# RaspiLink.net
KiCad netlist of a schematic drawn in EAGLE
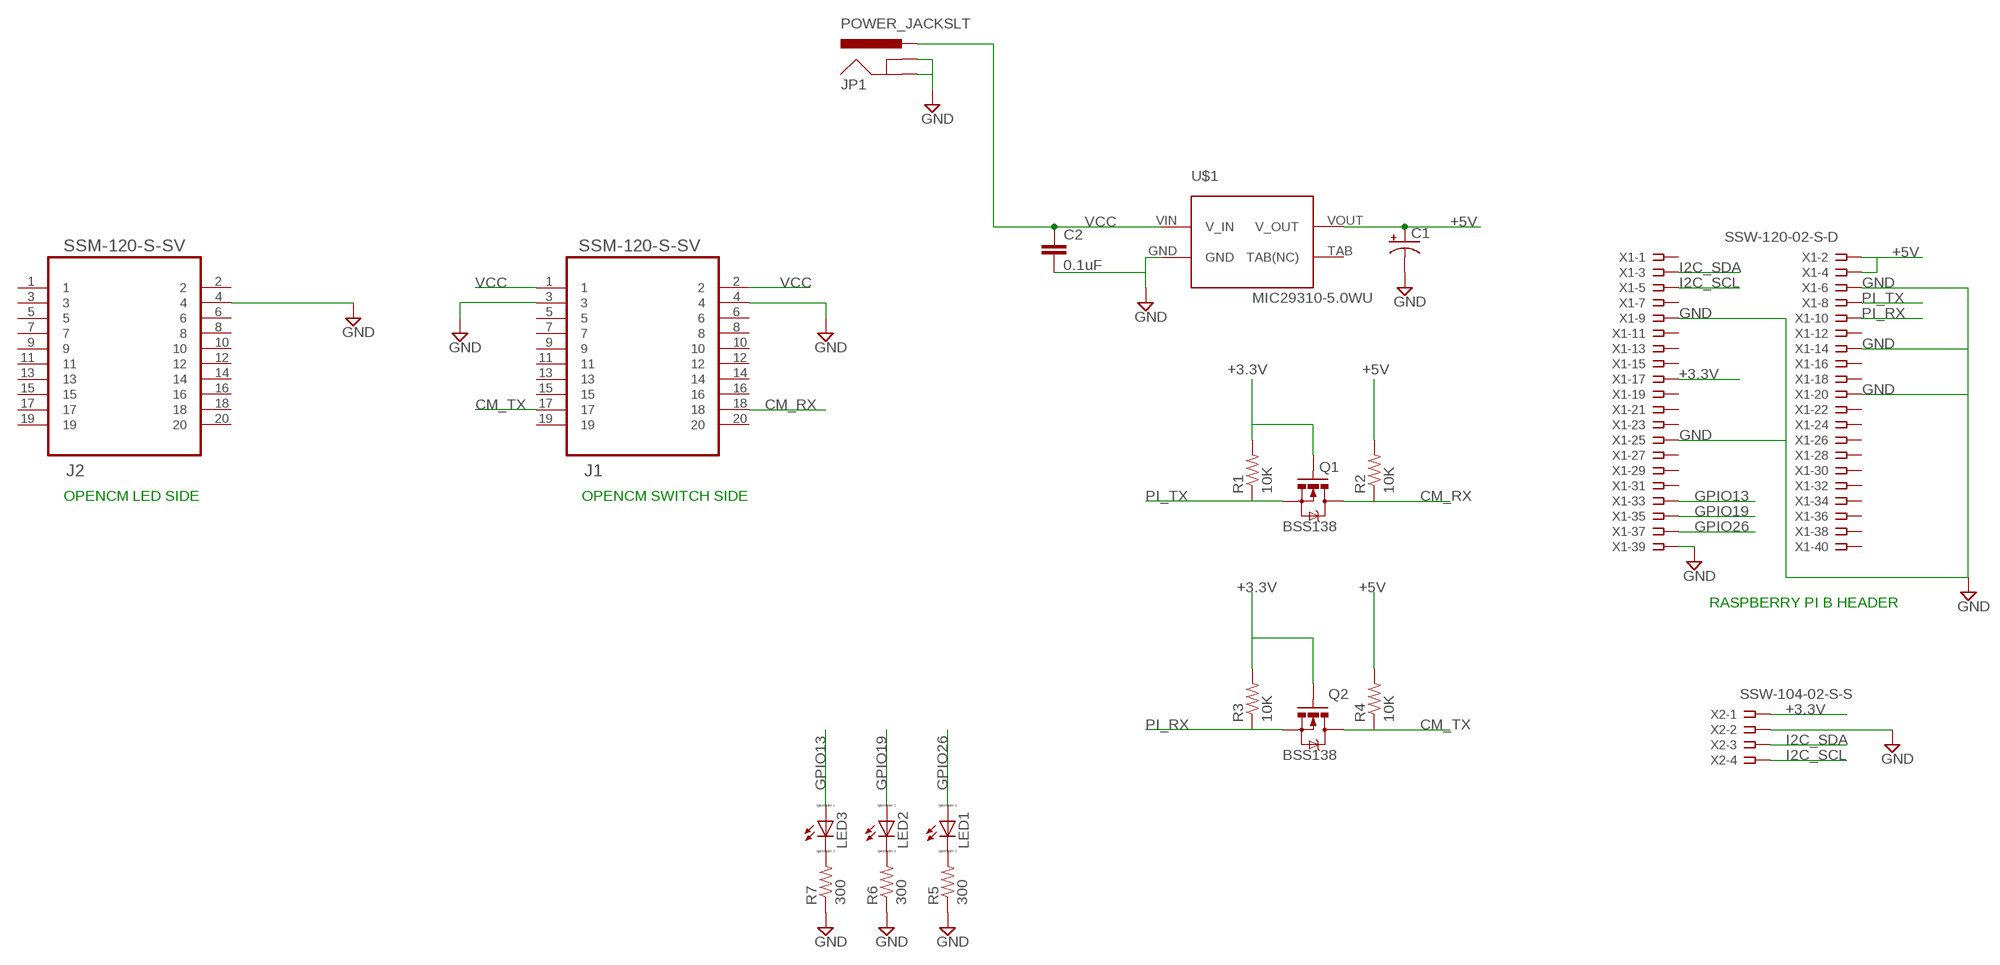
[diagram p0: schematic, sheet 1]

(export (version "E")
  (design (tool "Eeschema 10.0.6"))
  (components
    (comp (ref "C1")
      (value "100UF-25V-20%(PTH)")
      (footprint "eagle-import:CPOL-RADIAL-100UF-25V")
      (libsource (lib "eagle-import") (part "100UF-25V-20%(PTH)"))
    )
    (comp (ref "C2")
      (value "0.1uF")
      (footprint "eagle-import:0603-CAP")
      (libsource (lib "eagle-import") (part "0.1UF-25V-5%(0603)"))
    )
    (comp (ref "J1")
      (value "SSM-120-S-SV")
      (footprint "eagle-import:SAMTEC_SSM-120-S-SV")
      (libsource (lib "eagle-import") (part "SSM-120-S-SV"))
    )
    (comp (ref "J2")
      (value "SSM-120-S-SV")
      (footprint "eagle-import:SAMTEC_SSM-120-S-SV")
      (libsource (lib "eagle-import") (part "SSM-120-S-SV"))
    )
    (comp (ref "JP1")
      (value "POWER_JACKSLT")
      (footprint "eagle-import:POWER_JACK_SLOT")
      (libsource (lib "eagle-import") (part "POWER_JACKSLT"))
    )
    (comp (ref "LED1")
      (value "LED_ELD260")
      (footprint "eagle-import:LED_LD260")
      (libsource (lib "eagle-import") (part "LED_ELD260"))
    )
    (comp (ref "LED2")
      (value "LED_ELD260")
      (footprint "eagle-import:LED_LD260")
      (libsource (lib "eagle-import") (part "LED_ELD260"))
    )
    (comp (ref "LED3")
      (value "LED_ELD260")
      (footprint "eagle-import:LED_LD260")
      (libsource (lib "eagle-import") (part "LED_ELD260"))
    )
    (comp (ref "Q1")
      (value "MOSFET-NCHANNELBSS123LT1G")
      (footprint "eagle-import:SOT23-3")
      (fields (field (name "PROD_ID") "TRANS-08345") (field (name "PROD_ID_1") "BSS138"))
      (libsource (lib "eagle-import") (part "MOSFET-NCHANNELBSS123LT1G"))
    )
    (comp (ref "Q2")
      (value "MOSFET-NCHANNELBSS123LT1G")
      (footprint "eagle-import:SOT23-3")
      (fields (field (name "PROD_ID") "TRANS-08345") (field (name "PROD_ID_1") "BSS138"))
      (libsource (lib "eagle-import") (part "MOSFET-NCHANNELBSS123LT1G"))
    )
    (comp (ref "R1")
      (value "10K")
      (footprint "eagle-import:0603-RES")
      (libsource (lib "eagle-import") (part "RESISTOR0603-RES"))
    )
    (comp (ref "R2")
      (value "10K")
      (footprint "eagle-import:0603-RES")
      (libsource (lib "eagle-import") (part "RESISTOR0603-RES"))
    )
    (comp (ref "R3")
      (value "10K")
      (footprint "eagle-import:0603-RES")
      (libsource (lib "eagle-import") (part "RESISTOR0603-RES"))
    )
    (comp (ref "R4")
      (value "10K")
      (footprint "eagle-import:0603-RES")
      (libsource (lib "eagle-import") (part "RESISTOR0603-RES"))
    )
    (comp (ref "R5")
      (value "300")
      (footprint "eagle-import:0603-RES")
      (libsource (lib "eagle-import") (part "RESISTOR0603-RES"))
    )
    (comp (ref "R6")
      (value "300")
      (footprint "eagle-import:0603-RES")
      (libsource (lib "eagle-import") (part "RESISTOR0603-RES"))
    )
    (comp (ref "R7")
      (value "300")
      (footprint "eagle-import:0603-RES")
      (libsource (lib "eagle-import") (part "RESISTOR0603-RES"))
    )
    (comp (ref "U$1")
      (value "MIC29310-5.0WU")
      (footprint "eagle-import:TO-263-3")
      (libsource (lib "eagle-import") (part "MIC29310-5.0WU"))
    )
    (comp (ref "X1")
      (value "SSW-120-02-S-D")
      (footprint "eagle-import:SSW-120-02-S-D")
      (libsource (lib "eagle-import") (part "SSW-120-02-S-D"))
    )
    (comp (ref "X2")
      (value "SSW-104-02-S-S")
      (footprint "eagle-import:SSW-104-02-S-S")
      (libsource (lib "eagle-import") (part "SSW-104-02-S-S"))
    )
  )
  (nets
    (net (code "1") (name "/+3.3V") (class "Default")
      (node (ref "Q1") (pin "1") (pinfunction "G_1") (pintype "passive"))
      (node (ref "Q2") (pin "1") (pinfunction "G_1") (pintype "passive"))
      (node (ref "R1") (pin "2") (pinfunction "2_2") (pintype "passive"))
      (node (ref "R3") (pin "2") (pinfunction "2_2") (pintype "passive"))
      (node (ref "X1") (pin "17") (pinfunction "1_17") (pintype "passive"))
      (node (ref "X2") (pin "1") (pinfunction "1_1") (pintype "passive"))
    )
    (net (code "2") (name "/+5V") (class "Default")
      (node (ref "C1") (pin "1") (pinfunction "+_1") (pintype "passive"))
      (node (ref "R2") (pin "2") (pinfunction "2_2") (pintype "passive"))
      (node (ref "R4") (pin "2") (pinfunction "2_2") (pintype "passive"))
      (node (ref "U$1") (pin "VOUT") (pinfunction "V_OUT_VOUT") (pintype "bidirectional"))
      (node (ref "X1") (pin "2") (pinfunction "1_2") (pintype "passive"))
      (node (ref "X1") (pin "4") (pinfunction "1_4") (pintype "passive"))
    )
    (net (code "3") (name "/CM_RX") (class "Default")
      (node (ref "J1") (pin "18") (pinfunction "18_18") (pintype "passive"))
      (node (ref "Q1") (pin "3") (pinfunction "D_3") (pintype "passive"))
      (node (ref "R2") (pin "1") (pinfunction "1_1") (pintype "passive"))
    )
    (net (code "4") (name "/CM_TX") (class "Default")
      (node (ref "J1") (pin "17") (pinfunction "17_17") (pintype "passive"))
      (node (ref "Q2") (pin "3") (pinfunction "D_3") (pintype "passive"))
      (node (ref "R4") (pin "1") (pinfunction "1_1") (pintype "passive"))
    )
    (net (code "5") (name "/GPIO13") (class "Default")
      (node (ref "LED3") (pin "A") (pinfunction "A_A") (pintype "passive"))
      (node (ref "X1") (pin "33") (pinfunction "1_33") (pintype "passive"))
    )
    (net (code "6") (name "/GPIO19") (class "Default")
      (node (ref "LED2") (pin "A") (pinfunction "A_A") (pintype "passive"))
      (node (ref "X1") (pin "35") (pinfunction "1_35") (pintype "passive"))
    )
    (net (code "7") (name "/GPIO26") (class "Default")
      (node (ref "LED1") (pin "A") (pinfunction "A_A") (pintype "passive"))
      (node (ref "X1") (pin "37") (pinfunction "1_37") (pintype "passive"))
    )
    (net (code "8") (name "/I2C_SCL") (class "Default")
      (node (ref "X1") (pin "5") (pinfunction "1_5") (pintype "passive"))
      (node (ref "X2") (pin "4") (pinfunction "1_4") (pintype "passive"))
    )
    (net (code "9") (name "/I2C_SDA") (class "Default")
      (node (ref "X1") (pin "3") (pinfunction "1_3") (pintype "passive"))
      (node (ref "X2") (pin "3") (pinfunction "1_3") (pintype "passive"))
    )
    (net (code "10") (name "/PI_RX") (class "Default")
      (node (ref "Q2") (pin "2") (pinfunction "S_2") (pintype "passive"))
      (node (ref "R3") (pin "1") (pinfunction "1_1") (pintype "passive"))
      (node (ref "X1") (pin "10") (pinfunction "1_10") (pintype "passive"))
    )
    (net (code "11") (name "/PI_TX") (class "Default")
      (node (ref "Q1") (pin "2") (pinfunction "S_2") (pintype "passive"))
      (node (ref "R1") (pin "1") (pinfunction "1_1") (pintype "passive"))
      (node (ref "X1") (pin "8") (pinfunction "1_8") (pintype "passive"))
    )
    (net (code "12") (name "/VCC") (class "Default")
      (node (ref "C2") (pin "1") (pinfunction "1_1") (pintype "passive"))
      (node (ref "J1") (pin "1") (pinfunction "1_1") (pintype "passive"))
      (node (ref "J1") (pin "2") (pinfunction "2_2") (pintype "passive"))
      (node (ref "JP1") (pin "PWR") (pinfunction "PWR_PWR") (pintype "bidirectional"))
      (node (ref "U$1") (pin "VIN") (pinfunction "V_IN_VIN") (pintype "bidirectional"))
    )
    (net (code "13") (name "GND") (class "Default")
      (node (ref "C1") (pin "2") (pinfunction "-_2") (pintype "passive"))
      (node (ref "C2") (pin "2") (pinfunction "2_2") (pintype "passive"))
      (node (ref "J1") (pin "3") (pinfunction "3_3") (pintype "passive"))
      (node (ref "J1") (pin "4") (pinfunction "4_4") (pintype "passive"))
      (node (ref "J2") (pin "4") (pinfunction "4_4") (pintype "passive"))
      (node (ref "JP1") (pin "GND@1") (pinfunction "GNDBREAK_GND@1") (pintype "bidirectional"))
      (node (ref "JP1") (pin "GND@2") (pinfunction "GND_GND@2") (pintype "bidirectional"))
      (node (ref "R5") (pin "1") (pinfunction "1_1") (pintype "passive"))
      (node (ref "R6") (pin "1") (pinfunction "1_1") (pintype "passive"))
      (node (ref "R7") (pin "1") (pinfunction "1_1") (pintype "passive"))
      (node (ref "U$1") (pin "GND") (pinfunction "GND_GND") (pintype "bidirectional"))
      (node (ref "X1") (pin "14") (pinfunction "1_14") (pintype "passive"))
      (node (ref "X1") (pin "20") (pinfunction "1_20") (pintype "passive"))
      (node (ref "X1") (pin "25") (pinfunction "1_25") (pintype "passive"))
      (node (ref "X1") (pin "39") (pinfunction "1_39") (pintype "passive"))
      (node (ref "X1") (pin "6") (pinfunction "1_6") (pintype "passive"))
      (node (ref "X1") (pin "9") (pinfunction "1_9") (pintype "passive"))
      (node (ref "X2") (pin "2") (pinfunction "1_2") (pintype "passive"))
    )
    (net (code "14") (name "Net-(LED1-C)") (class "Default")
      (node (ref "LED1") (pin "K") (pinfunction "C_K") (pintype "passive"))
      (node (ref "R5") (pin "2") (pinfunction "2_2") (pintype "passive"))
    )
    (net (code "15") (name "Net-(LED2-C)") (class "Default")
      (node (ref "LED2") (pin "K") (pinfunction "C_K") (pintype "passive"))
      (node (ref "R6") (pin "2") (pinfunction "2_2") (pintype "passive"))
    )
    (net (code "16") (name "Net-(LED3-C)") (class "Default")
      (node (ref "LED3") (pin "K") (pinfunction "C_K") (pintype "passive"))
      (node (ref "R7") (pin "2") (pinfunction "2_2") (pintype "passive"))
    )
    (net (code "17") (name "unconnected-(J1-Pad5)") (class "Default")
      (node (ref "J1") (pin "5") (pinfunction "5_5") (pintype "passive"))
    )
    (net (code "18") (name "unconnected-(J1-Pad6)") (class "Default")
      (node (ref "J1") (pin "6") (pinfunction "6_6") (pintype "passive"))
    )
    (net (code "19") (name "unconnected-(J1-Pad7)") (class "Default")
      (node (ref "J1") (pin "7") (pinfunction "7_7") (pintype "passive"))
    )
    (net (code "20") (name "unconnected-(J1-Pad8)") (class "Default")
      (node (ref "J1") (pin "8") (pinfunction "8_8") (pintype "passive"))
    )
    (net (code "21") (name "unconnected-(J1-Pad9)") (class "Default")
      (node (ref "J1") (pin "9") (pinfunction "9_9") (pintype "passive"))
    )
    (net (code "22") (name "unconnected-(J1-Pad10)") (class "Default")
      (node (ref "J1") (pin "10") (pinfunction "10_10") (pintype "passive"))
    )
    (net (code "23") (name "unconnected-(J1-Pad11)") (class "Default")
      (node (ref "J1") (pin "11") (pinfunction "11_11") (pintype "passive"))
    )
    (net (code "24") (name "unconnected-(J1-Pad12)") (class "Default")
      (node (ref "J1") (pin "12") (pinfunction "12_12") (pintype "passive"))
    )
    (net (code "25") (name "unconnected-(J1-Pad13)") (class "Default")
      (node (ref "J1") (pin "13") (pinfunction "13_13") (pintype "passive"))
    )
    (net (code "26") (name "unconnected-(J1-Pad14)") (class "Default")
      (node (ref "J1") (pin "14") (pinfunction "14_14") (pintype "passive"))
    )
    (net (code "27") (name "unconnected-(J1-Pad15)") (class "Default")
      (node (ref "J1") (pin "15") (pinfunction "15_15") (pintype "passive"))
    )
    (net (code "28") (name "unconnected-(J1-Pad16)") (class "Default")
      (node (ref "J1") (pin "16") (pinfunction "16_16") (pintype "passive"))
    )
    (net (code "29") (name "unconnected-(J1-Pad19)") (class "Default")
      (node (ref "J1") (pin "19") (pinfunction "19_19") (pintype "passive"))
    )
    (net (code "30") (name "unconnected-(J1-Pad20)") (class "Default")
      (node (ref "J1") (pin "20") (pinfunction "20_20") (pintype "passive"))
    )
    (net (code "31") (name "unconnected-(J2-Pad1)") (class "Default")
      (node (ref "J2") (pin "1") (pinfunction "1_1") (pintype "passive"))
    )
    (net (code "32") (name "unconnected-(J2-Pad2)") (class "Default")
      (node (ref "J2") (pin "2") (pinfunction "2_2") (pintype "passive"))
    )
    (net (code "33") (name "unconnected-(J2-Pad3)") (class "Default")
      (node (ref "J2") (pin "3") (pinfunction "3_3") (pintype "passive"))
    )
    (net (code "34") (name "unconnected-(J2-Pad5)") (class "Default")
      (node (ref "J2") (pin "5") (pinfunction "5_5") (pintype "passive"))
    )
    (net (code "35") (name "unconnected-(J2-Pad6)") (class "Default")
      (node (ref "J2") (pin "6") (pinfunction "6_6") (pintype "passive"))
    )
    (net (code "36") (name "unconnected-(J2-Pad7)") (class "Default")
      (node (ref "J2") (pin "7") (pinfunction "7_7") (pintype "passive"))
    )
    (net (code "37") (name "unconnected-(J2-Pad8)") (class "Default")
      (node (ref "J2") (pin "8") (pinfunction "8_8") (pintype "passive"))
    )
    (net (code "38") (name "unconnected-(J2-Pad9)") (class "Default")
      (node (ref "J2") (pin "9") (pinfunction "9_9") (pintype "passive"))
    )
    (net (code "39") (name "unconnected-(J2-Pad10)") (class "Default")
      (node (ref "J2") (pin "10") (pinfunction "10_10") (pintype "passive"))
    )
    (net (code "40") (name "unconnected-(J2-Pad11)") (class "Default")
      (node (ref "J2") (pin "11") (pinfunction "11_11") (pintype "passive"))
    )
    (net (code "41") (name "unconnected-(J2-Pad12)") (class "Default")
      (node (ref "J2") (pin "12") (pinfunction "12_12") (pintype "passive"))
    )
    (net (code "42") (name "unconnected-(J2-Pad13)") (class "Default")
      (node (ref "J2") (pin "13") (pinfunction "13_13") (pintype "passive"))
    )
    (net (code "43") (name "unconnected-(J2-Pad14)") (class "Default")
      (node (ref "J2") (pin "14") (pinfunction "14_14") (pintype "passive"))
    )
    (net (code "44") (name "unconnected-(J2-Pad15)") (class "Default")
      (node (ref "J2") (pin "15") (pinfunction "15_15") (pintype "passive"))
    )
    (net (code "45") (name "unconnected-(J2-Pad16)") (class "Default")
      (node (ref "J2") (pin "16") (pinfunction "16_16") (pintype "passive"))
    )
    (net (code "46") (name "unconnected-(J2-Pad17)") (class "Default")
      (node (ref "J2") (pin "17") (pinfunction "17_17") (pintype "passive"))
    )
    (net (code "47") (name "unconnected-(J2-Pad18)") (class "Default")
      (node (ref "J2") (pin "18") (pinfunction "18_18") (pintype "passive"))
    )
    (net (code "48") (name "unconnected-(J2-Pad19)") (class "Default")
      (node (ref "J2") (pin "19") (pinfunction "19_19") (pintype "passive"))
    )
    (net (code "49") (name "unconnected-(J2-Pad20)") (class "Default")
      (node (ref "J2") (pin "20") (pinfunction "20_20") (pintype "passive"))
    )
    (net (code "50") (name "unconnected-(U$1-TAB(NC)-PadTAB)") (class "Default")
      (node (ref "U$1") (pin "TAB") (pinfunction "TAB(NC)_TAB") (pintype "bidirectional"))
    )
    (net (code "51") (name "unconnected-(X1-Pad1)") (class "Default")
      (node (ref "X1") (pin "1") (pinfunction "1_1") (pintype "passive"))
    )
    (net (code "52") (name "unconnected-(X1AB-1-Pad34)") (class "Default")
      (node (ref "X1") (pin "34") (pinfunction "1_34") (pintype "passive"))
    )
    (net (code "53") (name "unconnected-(X1AD-1-Pad36)") (class "Default")
      (node (ref "X1") (pin "36") (pinfunction "1_36") (pintype "passive"))
    )
    (net (code "54") (name "unconnected-(X1AF-1-Pad38)") (class "Default")
      (node (ref "X1") (pin "38") (pinfunction "1_38") (pintype "passive"))
    )
    (net (code "55") (name "unconnected-(X1AI-1-Pad40)") (class "Default")
      (node (ref "X1") (pin "40") (pinfunction "1_40") (pintype "passive"))
    )
    (net (code "56") (name "unconnected-(X1AL-1-Pad7)") (class "Default")
      (node (ref "X1") (pin "7") (pinfunction "1_7") (pintype "passive"))
    )
    (net (code "57") (name "unconnected-(X1C-1-Pad11)") (class "Default")
      (node (ref "X1") (pin "11") (pinfunction "1_11") (pintype "passive"))
    )
    (net (code "58") (name "unconnected-(X1D-1-Pad12)") (class "Default")
      (node (ref "X1") (pin "12") (pinfunction "1_12") (pintype "passive"))
    )
    (net (code "59") (name "unconnected-(X1E-1-Pad13)") (class "Default")
      (node (ref "X1") (pin "13") (pinfunction "1_13") (pintype "passive"))
    )
    (net (code "60") (name "unconnected-(X1G-1-Pad15)") (class "Default")
      (node (ref "X1") (pin "15") (pinfunction "1_15") (pintype "passive"))
    )
    (net (code "61") (name "unconnected-(X1H-1-Pad16)") (class "Default")
      (node (ref "X1") (pin "16") (pinfunction "1_16") (pintype "passive"))
    )
    (net (code "62") (name "unconnected-(X1J-1-Pad18)") (class "Default")
      (node (ref "X1") (pin "18") (pinfunction "1_18") (pintype "passive"))
    )
    (net (code "63") (name "unconnected-(X1K-1-Pad19)") (class "Default")
      (node (ref "X1") (pin "19") (pinfunction "1_19") (pintype "passive"))
    )
    (net (code "64") (name "unconnected-(X1N-1-Pad21)") (class "Default")
      (node (ref "X1") (pin "21") (pinfunction "1_21") (pintype "passive"))
    )
    (net (code "65") (name "unconnected-(X1O-1-Pad22)") (class "Default")
      (node (ref "X1") (pin "22") (pinfunction "1_22") (pintype "passive"))
    )
    (net (code "66") (name "unconnected-(X1P-1-Pad23)") (class "Default")
      (node (ref "X1") (pin "23") (pinfunction "1_23") (pintype "passive"))
    )
    (net (code "67") (name "unconnected-(X1Q-1-Pad24)") (class "Default")
      (node (ref "X1") (pin "24") (pinfunction "1_24") (pintype "passive"))
    )
    (net (code "68") (name "unconnected-(X1S-1-Pad26)") (class "Default")
      (node (ref "X1") (pin "26") (pinfunction "1_26") (pintype "passive"))
    )
    (net (code "69") (name "unconnected-(X1T-1-Pad27)") (class "Default")
      (node (ref "X1") (pin "27") (pinfunction "1_27") (pintype "passive"))
    )
    (net (code "70") (name "unconnected-(X1U-1-Pad28)") (class "Default")
      (node (ref "X1") (pin "28") (pinfunction "1_28") (pintype "passive"))
    )
    (net (code "71") (name "unconnected-(X1V-1-Pad29)") (class "Default")
      (node (ref "X1") (pin "29") (pinfunction "1_29") (pintype "passive"))
    )
    (net (code "72") (name "unconnected-(X1X-1-Pad30)") (class "Default")
      (node (ref "X1") (pin "30") (pinfunction "1_30") (pintype "passive"))
    )
    (net (code "73") (name "unconnected-(X1Y-1-Pad31)") (class "Default")
      (node (ref "X1") (pin "31") (pinfunction "1_31") (pintype "passive"))
    )
    (net (code "74") (name "unconnected-(X1Z-1-Pad32)") (class "Default")
      (node (ref "X1") (pin "32") (pinfunction "1_32") (pintype "passive"))
    )
  )
)
